# DiffProbe.net
KiCad netlist of a schematic drawn in Altium Designer
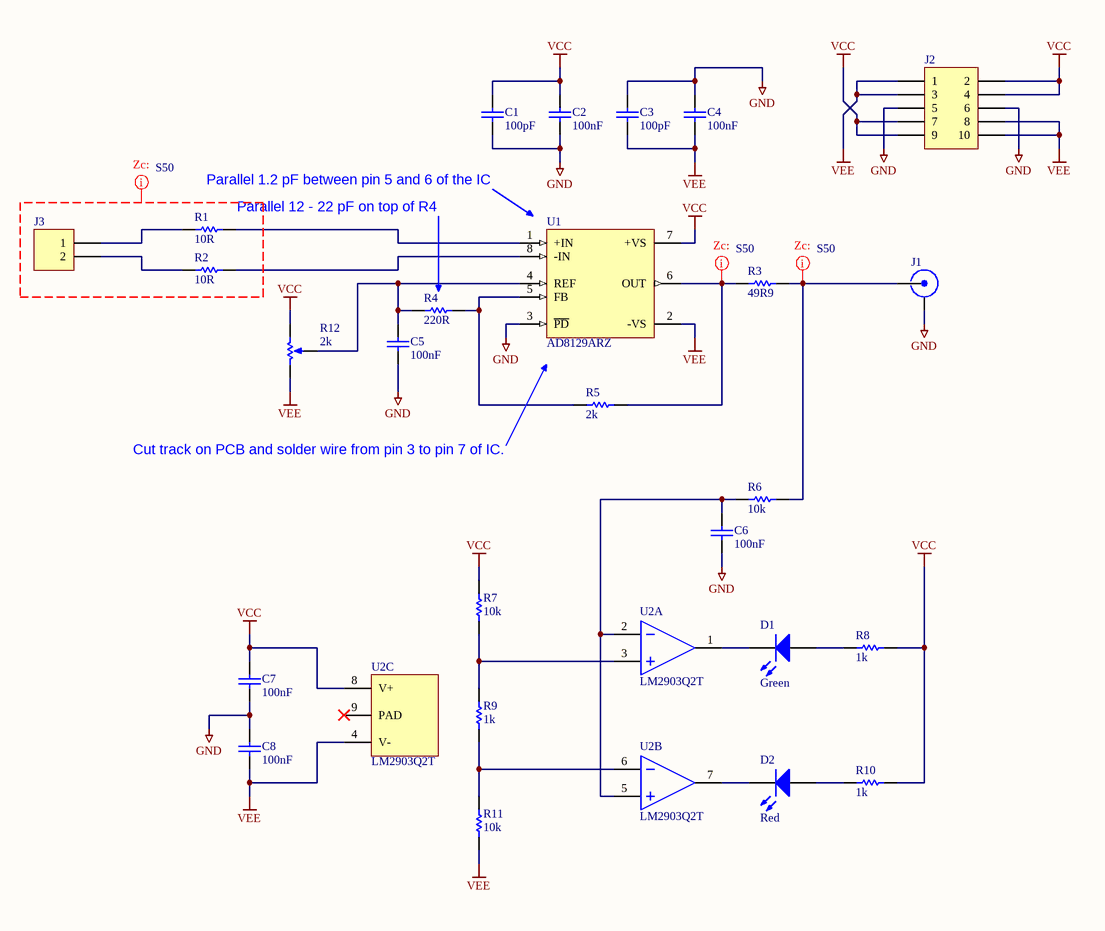
[diagram p0: DiffProbe.SchDoc]

(export (version "E")
  (design (tool "Eeschema 10.0.6"))
  (components
    (comp (ref "C1")
      (value "100pF")
      (footprint "Cap,SMD,0402")
      (description "100pF ±5% 50V Ceramic Capacitor C0G, NP0 0402 (1005 Metric)")
      (fields
        (field (name "VENDOR PART NUMBER") "490-10669-1-ND")
        (field (name "MANUFACTURER") "Murata Electronics")
        (field (name "CREATEDBY") "Judd Foster")
      )
      (libsource (lib "symbols") (part "CAP,Cer,100pF,50VDC,C0G/NP0,0402"))
    )
    (comp (ref "C2")
      (value "100nF")
      (footprint "Cap,SMD,0402")
      (description "0.1µF ±10% 25V Ceramic Capacitor X7R 0402 (1005 Metric)")
      (fields
        (field (name "VENDOR PART NUMBER") "490-14603-1-ND")
        (field (name "MANUFACTURER") "Murata Electronics")
        (field (name "CREATEDBY") "Judd Foster")
      )
      (libsource (lib "symbols") (part "CAP,Cer,100nF,25VDC,X7R,0402"))
    )
    (comp (ref "C3")
      (value "100pF")
      (footprint "Cap,SMD,0402")
      (description "100pF ±5% 50V Ceramic Capacitor C0G, NP0 0402 (1005 Metric)")
      (fields
        (field (name "VENDOR PART NUMBER") "490-10669-1-ND")
        (field (name "MANUFACTURER") "Murata Electronics")
        (field (name "CREATEDBY") "Judd Foster")
      )
      (libsource (lib "symbols") (part "CAP,Cer,100pF,50VDC,C0G/NP0,0402"))
    )
    (comp (ref "C4")
      (value "100nF")
      (footprint "Cap,SMD,0402")
      (description "0.1µF ±10% 25V Ceramic Capacitor X7R 0402 (1005 Metric)")
      (fields
        (field (name "VENDOR PART NUMBER") "490-14603-1-ND")
        (field (name "MANUFACTURER") "Murata Electronics")
        (field (name "CREATEDBY") "Judd Foster")
      )
      (libsource (lib "symbols") (part "CAP,Cer,100nF,25VDC,X7R,0402"))
    )
    (comp (ref "C5")
      (value "100nF")
      (footprint "Cap,SMD,0402")
      (description "0.1µF ±10% 25V Ceramic Capacitor X7R 0402 (1005 Metric)")
      (fields
        (field (name "VENDOR PART NUMBER") "490-14603-1-ND")
        (field (name "MANUFACTURER") "Murata Electronics")
        (field (name "CREATEDBY") "Judd Foster")
      )
      (libsource (lib "symbols") (part "CAP,Cer,100nF,25VDC,X7R,0402"))
    )
    (comp (ref "C6")
      (value "100nF")
      (footprint "Cap,SMD,0402")
      (description "0.1µF ±10% 25V Ceramic Capacitor X7R 0402 (1005 Metric)")
      (fields
        (field (name "VENDOR PART NUMBER") "490-14603-1-ND")
        (field (name "MANUFACTURER") "Murata Electronics")
        (field (name "CREATEDBY") "Judd Foster")
      )
      (libsource (lib "symbols") (part "CAP,Cer,100nF,25VDC,X7R,0402"))
    )
    (comp (ref "C7")
      (value "100nF")
      (footprint "Cap,SMD,0402")
      (description "0.1µF ±10% 25V Ceramic Capacitor X7R 0402 (1005 Metric)")
      (fields
        (field (name "VENDOR PART NUMBER") "490-14603-1-ND")
        (field (name "MANUFACTURER") "Murata Electronics")
        (field (name "CREATEDBY") "Judd Foster")
      )
      (libsource (lib "symbols") (part "CAP,Cer,100nF,25VDC,X7R,0402"))
    )
    (comp (ref "C8")
      (value "100nF")
      (footprint "Cap,SMD,0402")
      (description "0.1µF ±10% 25V Ceramic Capacitor X7R 0402 (1005 Metric)")
      (fields
        (field (name "VENDOR PART NUMBER") "490-14603-1-ND")
        (field (name "MANUFACTURER") "Murata Electronics")
        (field (name "CREATEDBY") "Judd Foster")
      )
      (libsource (lib "symbols") (part "CAP,Cer,100nF,25VDC,X7R,0402"))
    )
    (comp (ref "D1")
      (value "Green")
      (footprint "LED,0603")
      (description "Green 530nm LED Indication - Discrete 3V 0603 (1608 Metric)")
      (fields
        (field (name "MANUFACTURER") "Stanley Electric Co")
        (field (name "MANUFACTURER PART NUMBER") "THG1111C-0005-TR")
        (field (name "CREATEDBY") "Judd Foster")
      )
      (libsource (lib "symbols") (part "LED,Green,SMD,0603"))
    )
    (comp (ref "D2")
      (value "Red")
      (footprint "LED,0603")
      (description "Red 633nm LED Indication - Discrete 2V 0603 (1608 Metric)")
      (fields
        (field (name "MANUFACTURER") "Lite-On Inc.")
        (field (name "MANUFACTURER PART NUMBER") "LS Q976-NR-1")
        (field (name "CREATEDBY") "Judd Foster")
      )
      (libsource (lib "symbols") (part "LED,Red,SMD,0603"))
    )
    (comp (ref "J1")
      (value "CON-SMA-EDGE-S")
      (footprint "CONN,SMA,50OHM,EDGE")
      (description "SMA Connector Jack, Female Socket Board Edge, End Launch Solder")
      (fields
        (field (name "MANUFACTURER") "RF Solutions")
        (field (name "VENDOR PART NUMBER") "CON-SMA-EDGE-S-ND")
        (field (name "CREATEDBY") "Judd Foster")
      )
      (libsource (lib "symbols") (part "Conn,RF,SMA,Fem,50R,Edge,SMD"))
    )
    (comp (ref "J2")
      (value "Term,Header,5x2 Pin,1.27mm,SMD")
      (footprint "TERM,HEADER,5X2PIN,P1.27,SMD")
      (description "Connector Header Surface Mount 10 position 0.050\" (1.27mm)")
      (fields
        (field (name "VENDOR PART NUMBER") "609-3695-1-ND")
        (field (name "MANUFACTURER") "Amphenol ICC (FCI)")
        (field (name "CREATEDBY") "Judd Foster")
      )
      (libsource (lib "symbols") (part "Term,Header,5x2 Pin,1.27mm,SMD"))
    )
    (comp (ref "J3")
      (value "Term,Header,2 Pin,Top,2.54mm")
      (footprint "Term,Header,2Pin,2.54mm")
      (description "CONN HEADER VERT 2POS 2.54MM")
      (fields (field (name "CREATED BY") "Judd Foster"))
      (libsource (lib "symbols") (part "Term,Header,2 Pin,Top,2.54mm"))
    )
    (comp (ref "R1")
      (value "10R")
      (footprint "RES,0402")
      (description "10 Ohms ±1% 0.063W, 1/16W Chip Resistor 0402 (1005 Metric) Automotive AEC-Q200 Thick Film")
      (fields
        (field (name "MANUFACTURER") "Panasonic Electronic Components")
        (field (name "MANUFACTURER PART NUMBER") "ERJ-2RKF10R0X")
        (field (name "CREATEDBY") "Judd Foster")
      )
      (libsource (lib "symbols") (part "RES,10R,1%,0.063W,0402"))
    )
    (comp (ref "R2")
      (value "10R")
      (footprint "RES,0402")
      (description "10 Ohms ±1% 0.063W, 1/16W Chip Resistor 0402 (1005 Metric) Automotive AEC-Q200 Thick Film")
      (fields
        (field (name "MANUFACTURER") "Panasonic Electronic Components")
        (field (name "MANUFACTURER PART NUMBER") "ERJ-2RKF10R0X")
        (field (name "CREATEDBY") "Judd Foster")
      )
      (libsource (lib "symbols") (part "RES,10R,1%,0.063W,0402"))
    )
    (comp (ref "R3")
      (value "49R9")
      (footprint "RES,0402")
      (description "49.9 Ohms ±1% 0.063W, 1/16W Chip Resistor 0402 (1005 Metric) Moisture Resistant Thick Film")
      (fields
        (field (name "MANUFACTURER") "Yageo")
        (field (name "MANUFACTURER PART NUMBER") "RC0402FR-0749R9L")
        (field (name "CREATEDBY") "Judd Foster")
      )
      (libsource (lib "symbols") (part "RES,49R9,1%,0.063W,0402"))
    )
    (comp (ref "R4")
      (value "220R")
      (footprint "RES,0402")
      (description "220 Ohms ±1% 0.063W, 1/16W Chip Resistor 0402 (1005 Metric) Moisture Resistant Thick Film")
      (fields
        (field (name "MANUFACTURER") "Yageo")
        (field (name "MANUFACTURER PART NUMBER") "RC0402FR-07220RL")
        (field (name "CREATEDBY") "Judd Foster")
      )
      (libsource (lib "symbols") (part "RES,220R,1%,0.063W,0402"))
    )
    (comp (ref "R5")
      (value "2k")
      (footprint "RES,0402")
      (description "2 kOhms ±1% 0.063W, 1/16W Chip Resistor 0402 (1005 Metric) Automotive AEC-Q200 Thick Film")
      (fields
        (field (name "VENDOR PART NUMBER") "RMCF0402FT2K00CT-ND")
        (field (name "MANUFACTURER") "Stackpole Electronics Inc")
        (field (name "CREATEDBY") "Judd Foster")
      )
      (libsource (lib "symbols") (part "RES,2k,1%,0.063W,0402"))
    )
    (comp (ref "R6")
      (value "10k")
      (footprint "RES,0402")
      (description "10 kOhms ±5% 0.063W, 1/16W Chip Resistor 0402 (1005 Metric) Automotive AEC-Q200 Thick Film")
      (fields
        (field (name "VENDOR PART NUMBER") "RMCF0402JT10K0CT-ND")
        (field (name "MANUFACTURER") "Stackpole Electronics Inc")
        (field (name "CREATEDBY") "Judd Foster")
      )
      (libsource (lib "symbols") (part "RES,10k,5%,0.063W,0402"))
    )
    (comp (ref "R7")
      (value "10k")
      (footprint "RES,0402")
      (description "10 kOhms ±5% 0.063W, 1/16W Chip Resistor 0402 (1005 Metric) Automotive AEC-Q200 Thick Film")
      (fields
        (field (name "VENDOR PART NUMBER") "RMCF0402JT10K0CT-ND")
        (field (name "MANUFACTURER") "Stackpole Electronics Inc")
        (field (name "CREATEDBY") "Judd Foster")
      )
      (libsource (lib "symbols") (part "RES,10k,5%,0.063W,0402"))
    )
    (comp (ref "R8")
      (value "1k")
      (footprint "RES,0402")
      (description "1 kOhms ±5% 0.063W, 1/16W Chip Resistor 0402 (1005 Metric) Automotive AEC-Q200 Thick Film")
      (fields
        (field (name "VENDOR PART NUMBER") "RMCF0402JT1K00CT-ND")
        (field (name "MANUFACTURER") "Stackpole Electronics Inc")
        (field (name "CREATEDBY") "Judd Foster")
      )
      (libsource (lib "symbols") (part "RES,1k,5%,0.063W,0402"))
    )
    (comp (ref "R9")
      (value "1k")
      (footprint "RES,0402")
      (description "1 kOhms ±5% 0.063W, 1/16W Chip Resistor 0402 (1005 Metric) Automotive AEC-Q200 Thick Film")
      (fields
        (field (name "VENDOR PART NUMBER") "RMCF0402JT1K00CT-ND")
        (field (name "MANUFACTURER") "Stackpole Electronics Inc")
        (field (name "CREATEDBY") "Judd Foster")
      )
      (libsource (lib "symbols") (part "RES,1k,5%,0.063W,0402"))
    )
    (comp (ref "R10")
      (value "1k")
      (footprint "RES,0402")
      (description "1 kOhms ±5% 0.063W, 1/16W Chip Resistor 0402 (1005 Metric) Automotive AEC-Q200 Thick Film")
      (fields
        (field (name "VENDOR PART NUMBER") "RMCF0402JT1K00CT-ND")
        (field (name "MANUFACTURER") "Stackpole Electronics Inc")
        (field (name "CREATEDBY") "Judd Foster")
      )
      (libsource (lib "symbols") (part "RES,1k,5%,0.063W,0402"))
    )
    (comp (ref "R11")
      (value "10k")
      (footprint "RES,0402")
      (description "10 kOhms ±5% 0.063W, 1/16W Chip Resistor 0402 (1005 Metric) Automotive AEC-Q200 Thick Film")
      (fields
        (field (name "VENDOR PART NUMBER") "RMCF0402JT10K0CT-ND")
        (field (name "MANUFACTURER") "Stackpole Electronics Inc")
        (field (name "CREATEDBY") "Judd Foster")
      )
      (libsource (lib "symbols") (part "RES,10k,5%,0.063W,0402"))
    )
    (comp (ref "R12")
      (value "2k")
      (footprint "Res,Trim,5T,Top-Adj,SMD")
      (description "0.25W, 1/4W J Lead Surface Mount Trimmer Potentiometer Cermet Turn Top Adjustment")
      (fields
        (field (name "MANUFACTURER PART NUMBER") "3214W-202ECT-ND")
        (field (name "VENDOR PART NUMBER") "3214W-1-202E")
        (field (name "CREATEDBY") "Judd Foster")
      )
      (libsource (lib "symbols") (part "RES,Trim,5T,2k,0.75W,Top-Adj,SMD"))
    )
    (comp (ref "U1")
      (value "AD8129ARZ")
      (footprint "IC,SOIC-8,1.27mm,W3.9")
      (description "Differential Amplifier 1 Circuit 8-SOIC")
      (fields
        (field (name "MANUFACTURER") "Analog Devices Inc.")
        (field (name "VENDOR PART NUMBER") "505-AD8129ARZ-ND")
        (field (name "CREATEDBY") "Judd Foster")
      )
      (libsource (lib "symbols") (part "AD8129ARZ"))
    )
    (comp (ref "U2")
      (value "LM2903Q2T")
      (footprint "IC,DFN-8,P0.5,PAD")
      (description "Comparator Differential CMOS, DTL, ECL, TTL 8-DFN (2x2)")
      (fields
        (field (name "MANUFACTURER") "STMicroelectronics")
        (field (name "VENDOR PART NUMBER") "497-13503-1-ND")
        (field (name "CREATEDBY") "Judd Foster")
      )
      (libsource (lib "symbols") (part "LM2903Q2T"))
    )
  )
  (nets
    (net (code "1") (name "GND") (class "Default")
      (node (ref "C1") (pin "1") (pinfunction "1_1") (pintype "passive"))
      (node (ref "C2") (pin "1") (pinfunction "1_1") (pintype "passive"))
      (node (ref "C3") (pin "2") (pinfunction "2_2") (pintype "passive"))
      (node (ref "C4") (pin "2") (pinfunction "2_2") (pintype "passive"))
      (node (ref "C5") (pin "1") (pinfunction "1_1") (pintype "passive"))
      (node (ref "C6") (pin "1") (pinfunction "1_1") (pintype "passive"))
      (node (ref "C7") (pin "1") (pinfunction "1_1") (pintype "passive"))
      (node (ref "C8") (pin "2") (pinfunction "2_2") (pintype "passive"))
      (node (ref "J1") (pin "2") (pinfunction "GND_2") (pintype "passive"))
      (node (ref "J2") (pin "5") (pinfunction "5_5") (pintype "passive"))
      (node (ref "J2") (pin "6") (pinfunction "6_6") (pintype "passive"))
      (node (ref "U1") (pin "3") (pinfunction "~{PD}_3") (pintype "input"))
    )
    (net (code "2") (name "Net-(D1-A)") (class "Default")
      (node (ref "D1") (pin "1") (pinfunction "A_1") (pintype "passive"))
      (node (ref "R8") (pin "2") (pinfunction "2_2") (pintype "passive"))
    )
    (net (code "3") (name "Net-(D1-K)") (class "Default")
      (node (ref "D1") (pin "2") (pinfunction "K_2") (pintype "passive"))
      (node (ref "U2") (pin "1") (pinfunction "OUT1_1") (pintype "open_collector"))
    )
    (net (code "4") (name "Net-(D2-A)") (class "Default")
      (node (ref "D2") (pin "1") (pinfunction "A_1") (pintype "passive"))
      (node (ref "R10") (pin "2") (pinfunction "2_2") (pintype "passive"))
    )
    (net (code "5") (name "Net-(D2-K)") (class "Default")
      (node (ref "D2") (pin "2") (pinfunction "K_2") (pintype "passive"))
      (node (ref "U2") (pin "7") (pinfunction "OUT2_7") (pintype "open_collector"))
    )
    (net (code "6") (name "Net-(J1-RF)") (class "Default")
      (node (ref "J1") (pin "1") (pinfunction "RF_1") (pintype "passive"))
      (node (ref "R3") (pin "2") (pinfunction "2_2") (pintype "passive"))
      (node (ref "R6") (pin "1") (pinfunction "1_1") (pintype "passive"))
    )
    (net (code "7") (name "Net-(J3-Pad1)") (class "Default")
      (node (ref "J3") (pin "1") (pinfunction "1_1") (pintype "passive"))
      (node (ref "R1") (pin "1") (pinfunction "1_1") (pintype "passive"))
    )
    (net (code "8") (name "Net-(J3-Pad2)") (class "Default")
      (node (ref "J3") (pin "2") (pinfunction "2_2") (pintype "passive"))
      (node (ref "R2") (pin "1") (pinfunction "1_1") (pintype "passive"))
    )
    (net (code "9") (name "Net-(R12-TAP)") (class "Default")
      (node (ref "C5") (pin "2") (pinfunction "2_2") (pintype "passive"))
      (node (ref "R12") (pin "2") (pinfunction "TAP_2") (pintype "passive"))
      (node (ref "R4") (pin "1") (pinfunction "1_1") (pintype "passive"))
      (node (ref "U1") (pin "4") (pinfunction "REF_4") (pintype "input"))
    )
    (net (code "10") (name "Net-(U1-+IN)") (class "Default")
      (node (ref "R1") (pin "2") (pinfunction "2_2") (pintype "passive"))
      (node (ref "U1") (pin "1") (pinfunction "+IN_1") (pintype "input"))
    )
    (net (code "11") (name "Net-(U1--IN)") (class "Default")
      (node (ref "R2") (pin "2") (pinfunction "2_2") (pintype "passive"))
      (node (ref "U1") (pin "8") (pinfunction "-IN_8") (pintype "input"))
    )
    (net (code "12") (name "Net-(U1-FB)") (class "Default")
      (node (ref "R4") (pin "2") (pinfunction "2_2") (pintype "passive"))
      (node (ref "R5") (pin "1") (pinfunction "1_1") (pintype "passive"))
      (node (ref "U1") (pin "5") (pinfunction "FB_5") (pintype "input"))
    )
    (net (code "13") (name "Net-(U1-OUT)") (class "Default")
      (node (ref "R3") (pin "1") (pinfunction "1_1") (pintype "passive"))
      (node (ref "R5") (pin "2") (pinfunction "2_2") (pintype "passive"))
      (node (ref "U1") (pin "6") (pinfunction "OUT_6") (pintype "output"))
    )
    (net (code "14") (name "Net-(U2A-IN1+)") (class "Default")
      (node (ref "R7") (pin "1") (pinfunction "1_1") (pintype "passive"))
      (node (ref "R9") (pin "2") (pinfunction "2_2") (pintype "passive"))
      (node (ref "U2") (pin "3") (pinfunction "IN1+_3") (pintype "tri_state"))
    )
    (net (code "15") (name "Net-(U2A-IN1-)") (class "Default")
      (node (ref "C6") (pin "2") (pinfunction "2_2") (pintype "passive"))
      (node (ref "R6") (pin "2") (pinfunction "2_2") (pintype "passive"))
      (node (ref "U2") (pin "2") (pinfunction "IN1-_2") (pintype "tri_state"))
      (node (ref "U2") (pin "5") (pinfunction "IN2+_5") (pintype "tri_state"))
    )
    (net (code "16") (name "Net-(U2B-IN2-)") (class "Default")
      (node (ref "R11") (pin "2") (pinfunction "2_2") (pintype "passive"))
      (node (ref "R9") (pin "1") (pinfunction "1_1") (pintype "passive"))
      (node (ref "U2") (pin "6") (pinfunction "IN2-_6") (pintype "tri_state"))
    )
    (net (code "17") (name "VCC") (class "Default")
      (node (ref "C1") (pin "2") (pinfunction "2_2") (pintype "passive"))
      (node (ref "C2") (pin "2") (pinfunction "2_2") (pintype "passive"))
      (node (ref "C7") (pin "2") (pinfunction "2_2") (pintype "passive"))
      (node (ref "J2") (pin "2") (pinfunction "2_2") (pintype "passive"))
      (node (ref "J2") (pin "4") (pinfunction "4_4") (pintype "passive"))
      (node (ref "J2") (pin "7") (pinfunction "7_7") (pintype "passive"))
      (node (ref "J2") (pin "9") (pinfunction "9_9") (pintype "passive"))
      (node (ref "R10") (pin "1") (pinfunction "1_1") (pintype "passive"))
      (node (ref "R12") (pin "3") (pinfunction "TOP_3") (pintype "passive"))
      (node (ref "R7") (pin "2") (pinfunction "2_2") (pintype "passive"))
      (node (ref "R8") (pin "1") (pinfunction "1_1") (pintype "passive"))
      (node (ref "U1") (pin "7") (pinfunction "+VS_7") (pintype "power_in"))
      (node (ref "U2") (pin "8") (pinfunction "V+_8") (pintype "power_in"))
    )
    (net (code "18") (name "VEE") (class "Default")
      (node (ref "C3") (pin "1") (pinfunction "1_1") (pintype "passive"))
      (node (ref "C4") (pin "1") (pinfunction "1_1") (pintype "passive"))
      (node (ref "C8") (pin "1") (pinfunction "1_1") (pintype "passive"))
      (node (ref "J2") (pin "1") (pinfunction "1_1") (pintype "passive"))
      (node (ref "J2") (pin "10") (pinfunction "10_10") (pintype "passive"))
      (node (ref "J2") (pin "3") (pinfunction "3_3") (pintype "passive"))
      (node (ref "J2") (pin "8") (pinfunction "8_8") (pintype "passive"))
      (node (ref "R11") (pin "1") (pinfunction "1_1") (pintype "passive"))
      (node (ref "R12") (pin "1") (pinfunction "BOT_1") (pintype "passive"))
      (node (ref "U1") (pin "2") (pinfunction "-VS_2") (pintype "power_in"))
      (node (ref "U2") (pin "4") (pinfunction "V-_4") (pintype "power_in"))
    )
    (net (code "19") (name "unconnected-(U2C-PAD-Pad9)") (class "Default")
      (node (ref "U2") (pin "9") (pinfunction "PAD_9") (pintype "power_in+no_connect"))
    )
  )
)
